# PE_CAM_EZ_Bridge.net
KiCad netlist of a schematic drawn in Altium Designer
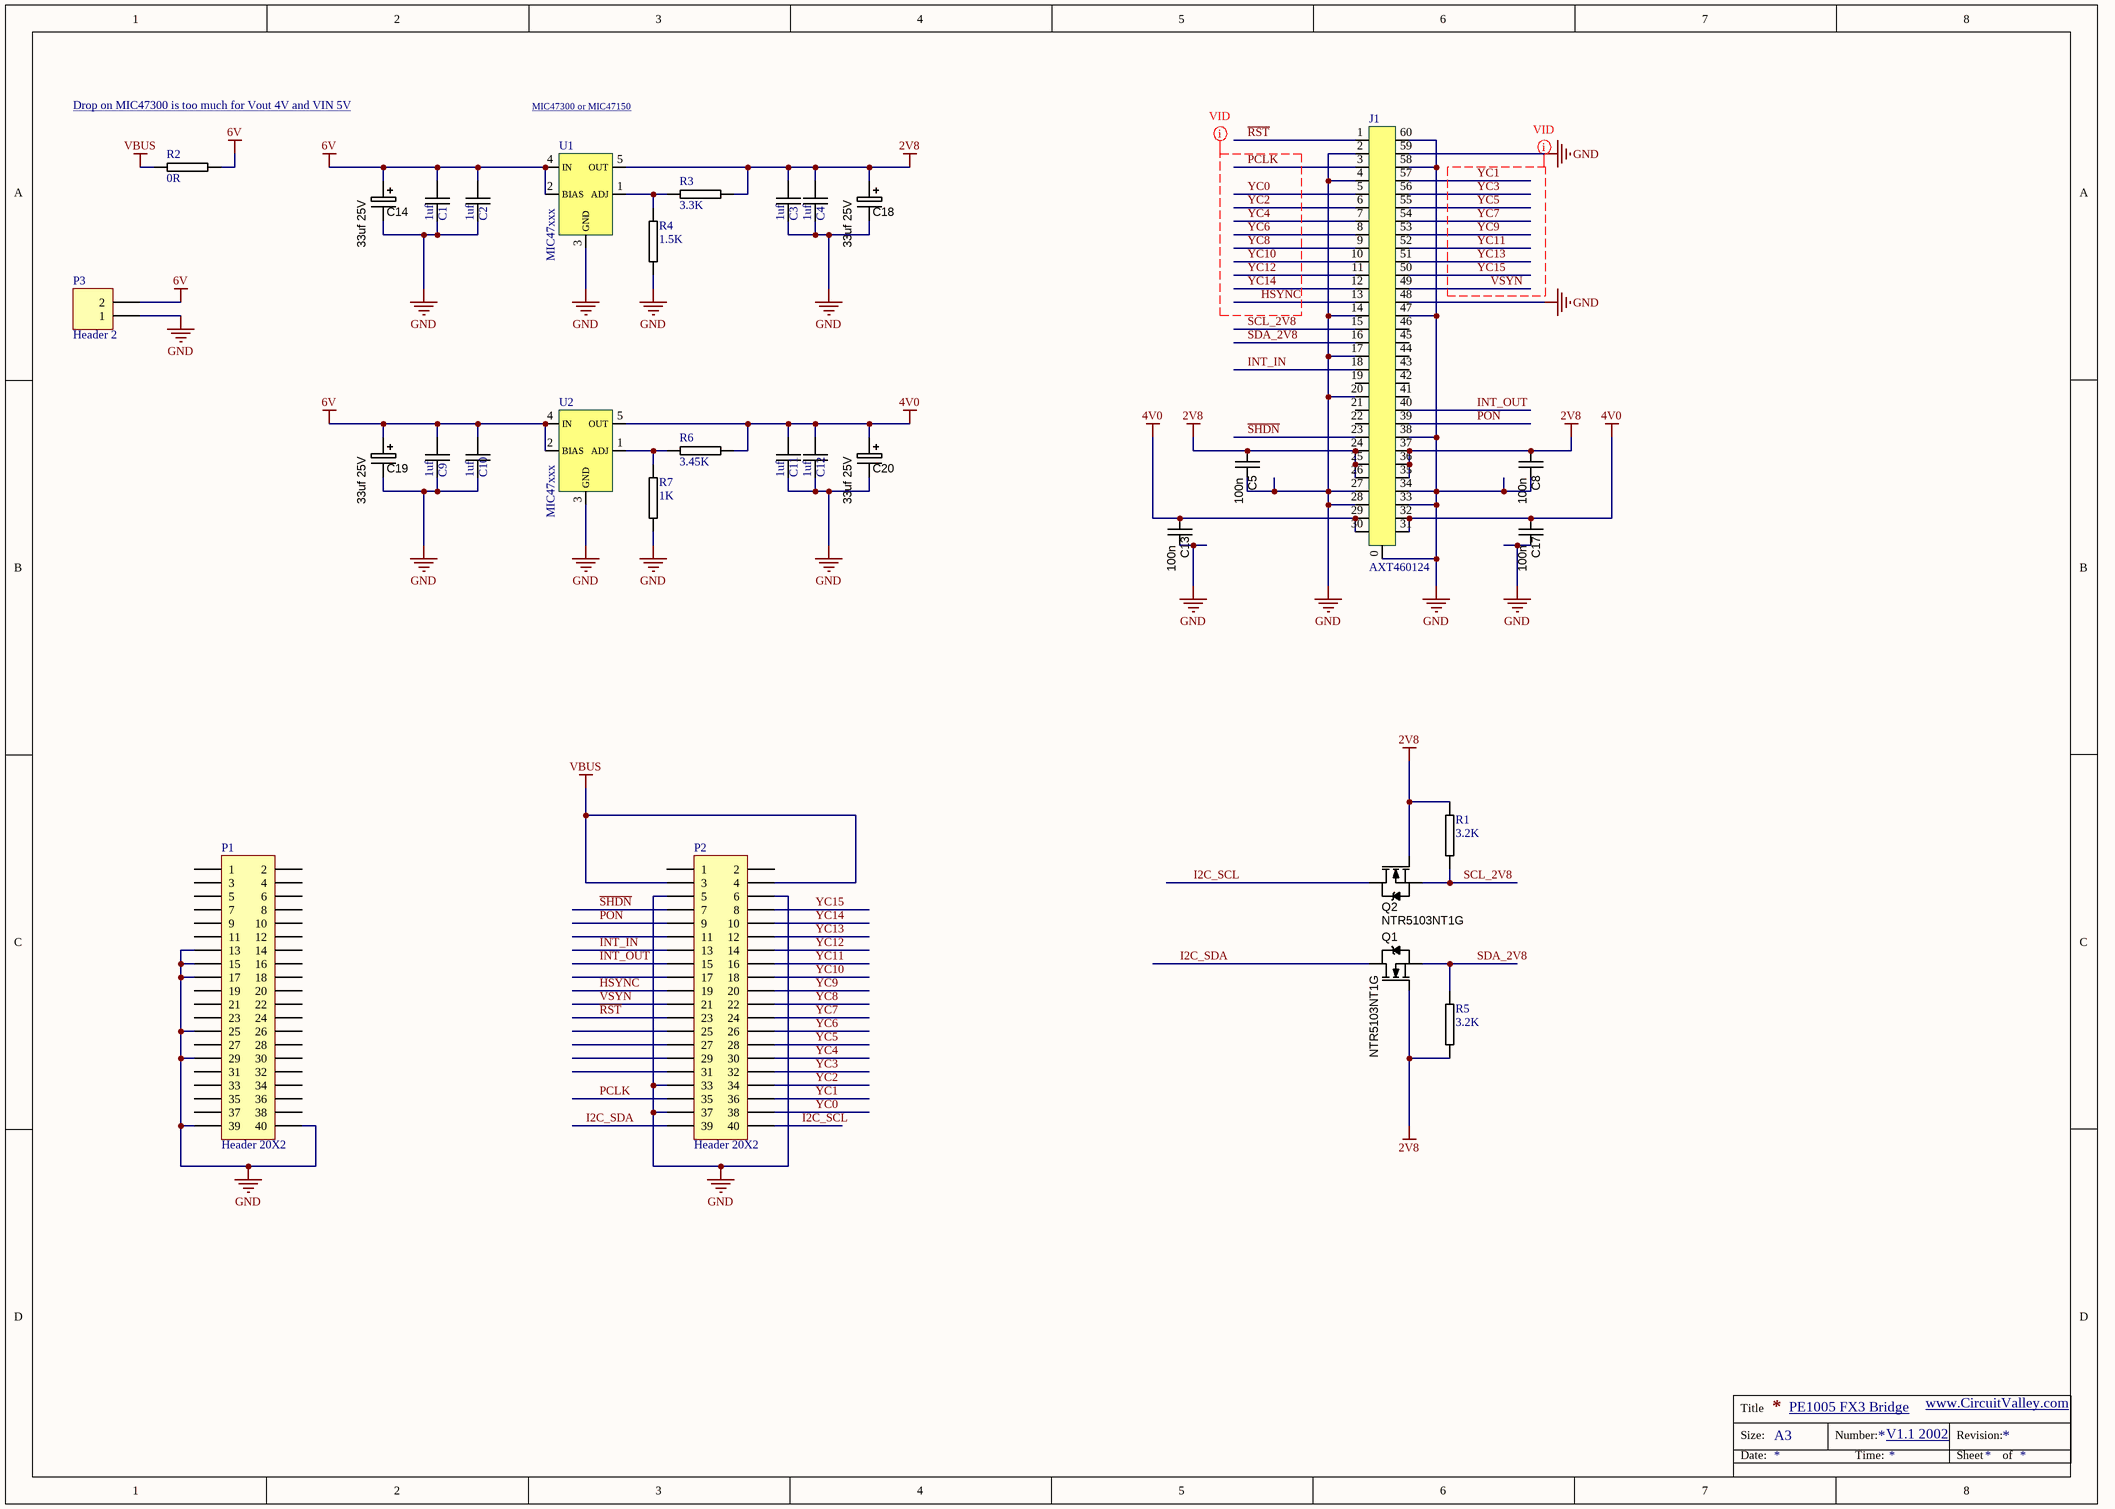
[diagram p0: PE_CAM_EZ_Bridge.SchDoc]

(export (version "E")
  (design (tool "Eeschema 10.0.6"))
  (components
    (comp (ref "C1")
      (value "1uf")
      (footprint "0805C-TBD")
      (description "CAPACITOR 0805 CERAMIC VALUE TO BE DETERMINED")
      (libsource (lib "Generic") (part "0805C-TBD"))
    )
    (comp (ref "C2")
      (value "1uf")
      (footprint "0805C-TBD")
      (description "CAPACITOR 0805 CERAMIC VALUE TO BE DETERMINED")
      (libsource (lib "Generic") (part "0805C-TBD"))
    )
    (comp (ref "C3")
      (value "1uf")
      (footprint "0805C-TBD")
      (description "CAPACITOR 0805 CERAMIC VALUE TO BE DETERMINED")
      (libsource (lib "Generic") (part "0805C-TBD"))
    )
    (comp (ref "C4")
      (value "1uf")
      (footprint "0805C-TBD")
      (description "CAPACITOR 0805 CERAMIC VALUE TO BE DETERMINED")
      (libsource (lib "Generic") (part "0805C-TBD"))
    )
    (comp (ref "C5")
      (value "100n")
      (footprint "CAPC1608N")
      (description "Capacitor SMD Cer 10pF 5% 50V NP0 0603")
      (fields (field (name "TOLERANCE") "±5%") (field (name "PART") "C0603X104K5RAC"))
      (libsource (lib "PBL - Capacitors") (part "CAPC_10p_0603_NP0_1%_50V"))
    )
    (comp (ref "C8")
      (value "100n")
      (footprint "CAPC1608N")
      (description "Capacitor SMD Cer 10pF 5% 50V NP0 0603")
      (fields (field (name "TOLERANCE") "±5%") (field (name "PART") "C0603X104K5RAC"))
      (libsource (lib "PBL - Capacitors") (part "CAPC_10p_0603_NP0_1%_50V"))
    )
    (comp (ref "C9")
      (value "1uf")
      (footprint "0805C-TBD")
      (description "CAPACITOR 0805 CERAMIC VALUE TO BE DETERMINED")
      (libsource (lib "Generic") (part "0805C-TBD"))
    )
    (comp (ref "C10")
      (value "1uf")
      (footprint "0805C-TBD")
      (description "CAPACITOR 0805 CERAMIC VALUE TO BE DETERMINED")
      (libsource (lib "Generic") (part "0805C-TBD"))
    )
    (comp (ref "C11")
      (value "1uf")
      (footprint "0805C-TBD")
      (description "CAPACITOR 0805 CERAMIC VALUE TO BE DETERMINED")
      (libsource (lib "Generic") (part "0805C-TBD"))
    )
    (comp (ref "C12")
      (value "1uf")
      (footprint "0805C-TBD")
      (description "CAPACITOR 0805 CERAMIC VALUE TO BE DETERMINED")
      (libsource (lib "Generic") (part "0805C-TBD"))
    )
    (comp (ref "C13")
      (value "100n")
      (footprint "CAPC1608N")
      (description "Capacitor SMD Cer 10pF 5% 50V NP0 0603")
      (fields (field (name "TOLERANCE") "±5%") (field (name "PART") "C0603X104K5RAC"))
      (libsource (lib "PBL - Capacitors") (part "CAPC_10p_0603_NP0_1%_50V"))
    )
    (comp (ref "C14")
      (value "33uf 25V")
      (footprint "CAPMP7343X310N")
      (description "Capacitor SMD Tant 330uF 20% 6V3 2917")
      (fields
        (field (name "TOLERANCE") "±20%")
        (field (name "MANUFACTURER PART NUMBER") "T520D337M006ATE015")
      )
      (libsource (lib "PBL - Capacitors") (part "CAPT_330u_2917_6V3"))
    )
    (comp (ref "C17")
      (value "100n")
      (footprint "CAPC1608N")
      (description "Capacitor SMD Cer 10pF 5% 50V NP0 0603")
      (fields (field (name "TOLERANCE") "±5%") (field (name "PART") "C0603X104K5RAC"))
      (libsource (lib "PBL - Capacitors") (part "CAPC_10p_0603_NP0_1%_50V"))
    )
    (comp (ref "C18")
      (value "33uf 25V")
      (footprint "CAPMP7343X310N")
      (description "Capacitor SMD Tant 330uF 20% 6V3 2917")
      (fields
        (field (name "TOLERANCE") "±20%")
        (field (name "MANUFACTURER PART NUMBER") "T520D337M006ATE015")
      )
      (libsource (lib "PBL - Capacitors") (part "CAPT_330u_2917_6V3"))
    )
    (comp (ref "C19")
      (value "33uf 25V")
      (footprint "CAPMP7343X310N")
      (description "Capacitor SMD Tant 330uF 20% 6V3 2917")
      (fields
        (field (name "TOLERANCE") "±20%")
        (field (name "MANUFACTURER PART NUMBER") "T520D337M006ATE015")
      )
      (libsource (lib "PBL - Capacitors") (part "CAPT_330u_2917_6V3"))
    )
    (comp (ref "C20")
      (value "33uf 25V")
      (footprint "CAPMP7343X310N")
      (description "Capacitor SMD Tant 330uF 20% 6V3 2917")
      (fields
        (field (name "TOLERANCE") "±20%")
        (field (name "MANUFACTURER PART NUMBER") "T520D337M006ATE015")
      )
      (libsource (lib "PBL - Capacitors") (part "CAPT_330u_2917_6V3"))
    )
    (comp (ref "J1")
      (value "AXT460124")
      (footprint "AXT460124")
      (libsource (lib "cvlib") (part "Connector 60 Pin"))
    )
    (comp (ref "P1")
      (value "Header 20X2")
      (footprint "HDR2X20")
      (description "Header, 20-Pin, Dual row")
      (fields (field (name "PUBLISHER") "Altium Limited"))
      (libsource (lib "Miscellaneous Connectors") (part "Header 20X2"))
    )
    (comp (ref "P2")
      (value "Header 20X2")
      (footprint "HDR2X20")
      (description "Header, 20-Pin, Dual row")
      (fields (field (name "PUBLISHER") "Altium Limited"))
      (libsource (lib "Miscellaneous Connectors") (part "Header 20X2"))
    )
    (comp (ref "P3")
      (value "Header 2")
      (footprint "HDR1X2")
      (description "Header, 2-Pin")
      (fields (field (name "PUBLISHER") "Altium Limited"))
      (libsource (lib "Miscellaneous Connectors") (part "Header 2"))
    )
    (comp (ref "Q1")
      (value "NTR5103NT1G")
      (footprint "SOT23-3")
      (description "MOSFET SMD N-CH 100V 170mA SOT23-3")
      (libsource (lib "PBL - Transistors") (part "MOSFET_BSS123"))
    )
    (comp (ref "Q2")
      (value "NTR5103NT1G")
      (footprint "SOT23-3")
      (description "MOSFET SMD N-CH 100V 170mA SOT23-3")
      (libsource (lib "PBL - Transistors") (part "MOSFET_BSS123"))
    )
    (comp (ref "R1")
      (value "3.2K")
      (footprint "0805R-5K6")
      (description "RESISTOR 0805 1/4 WATT THIN FILM")
      (fields (field (name "PART") "RC0805FR-075K6L"))
      (libsource (lib "Generic") (part "0805R-5K6"))
    )
    (comp (ref "R2")
      (value "0R")
      (footprint "0805R-5K6")
      (description "RESISTOR 0805 1/4 WATT THIN FILM")
      (fields (field (name "PART") "RC0805FR-075K6L"))
      (libsource (lib "Generic") (part "0805R-5K6"))
    )
    (comp (ref "R3")
      (value "3.3K")
      (footprint "0805R-5K6")
      (description "RESISTOR 0805 1/4 WATT THIN FILM")
      (fields (field (name "PART") "RC0805FR-075K6L"))
      (libsource (lib "Generic") (part "0805R-5K6"))
    )
    (comp (ref "R4")
      (value "1.5K")
      (footprint "0805R-5K6")
      (description "RESISTOR 0805 1/4 WATT THIN FILM")
      (fields (field (name "PART") "RC0805FR-075K6L"))
      (libsource (lib "Generic") (part "0805R-5K6"))
    )
    (comp (ref "R5")
      (value "3.2K")
      (footprint "0805R-5K6")
      (description "RESISTOR 0805 1/4 WATT THIN FILM")
      (fields (field (name "PART") "RC0805FR-075K6L"))
      (libsource (lib "Generic") (part "0805R-5K6"))
    )
    (comp (ref "R6")
      (value "3.45K")
      (footprint "0805R-5K6")
      (description "RESISTOR 0805 1/4 WATT THIN FILM")
      (fields (field (name "PART") "RC0805FR-075K6L"))
      (libsource (lib "Generic") (part "0805R-5K6"))
    )
    (comp (ref "R7")
      (value "1K")
      (footprint "0805R-5K6")
      (description "RESISTOR 0805 1/4 WATT THIN FILM")
      (fields (field (name "PART") "RC0805FR-075K6L"))
      (libsource (lib "Generic") (part "0805R-5K6"))
    )
    (comp (ref "U1")
      (value "MIC47xxx")
      (footprint "TO-252-5 DPAK 5")
      (description "MIC47xxx Regulator")
      (libsource (lib "cvlib") (part "MIC47xxx"))
    )
    (comp (ref "U2")
      (value "MIC47xxx")
      (footprint "TO-252-5 DPAK 5")
      (description "MIC47xxx Regulator")
      (libsource (lib "cvlib") (part "MIC47xxx"))
    )
  )
  (nets
    (net (code "1") (name "/HSYNC") (class "Default")
      (node (ref "J1") (pin "13") (pinfunction "74_13") (pintype "passive"))
      (node (ref "P2") (pin "19") (pinfunction "19_19") (pintype "passive"))
    )
    (net (code "2") (name "/I2C_SCL") (class "Default")
      (node (ref "P2") (pin "40") (pinfunction "40_40") (pintype "passive"))
      (node (ref "Q2") (pin "3") (pinfunction "D_3") (pintype "passive"))
    )
    (net (code "3") (name "/I2C_SDA") (class "Default")
      (node (ref "P2") (pin "39") (pinfunction "39_39") (pintype "passive"))
      (node (ref "Q1") (pin "3") (pinfunction "D_3") (pintype "passive"))
    )
    (net (code "4") (name "/INT_IN") (class "Default")
      (node (ref "J1") (pin "18") (pinfunction "79_18") (pintype "passive"))
      (node (ref "P2") (pin "13") (pinfunction "13_13") (pintype "passive"))
    )
    (net (code "5") (name "/INT_OUT") (class "Default")
      (node (ref "J1") (pin "40") (pinfunction "101_40") (pintype "passive"))
      (node (ref "P2") (pin "15") (pinfunction "15_15") (pintype "passive"))
    )
    (net (code "6") (name "/PCLK") (class "Default")
      (node (ref "J1") (pin "3") (pinfunction "64_3") (pintype "passive"))
      (node (ref "P2") (pin "35") (pinfunction "35_35") (pintype "passive"))
    )
    (net (code "7") (name "/PON") (class "Default")
      (node (ref "J1") (pin "39") (pinfunction "100_39") (pintype "passive"))
      (node (ref "P2") (pin "9") (pinfunction "9_9") (pintype "passive"))
    )
    (net (code "8") (name "/SCL_2V8") (class "Default")
      (node (ref "J1") (pin "15") (pinfunction "76_15") (pintype "passive"))
      (node (ref "Q2") (pin "2") (pinfunction "S_2") (pintype "passive"))
      (node (ref "R1") (pin "2") (pintype "passive"))
    )
    (net (code "9") (name "/SDA_2V8") (class "Default")
      (node (ref "J1") (pin "16") (pinfunction "77_16") (pintype "passive"))
      (node (ref "Q1") (pin "2") (pinfunction "S_2") (pintype "passive"))
      (node (ref "R5") (pin "1") (pintype "passive"))
    )
    (net (code "10") (name "/VSYN") (class "Default")
      (node (ref "J1") (pin "49") (pinfunction "110_49") (pintype "passive"))
      (node (ref "P2") (pin "21") (pinfunction "21_21") (pintype "passive"))
    )
    (net (code "11") (name "/YC0") (class "Default")
      (node (ref "J1") (pin "5") (pinfunction "66_5") (pintype "passive"))
      (node (ref "P2") (pin "38") (pinfunction "38_38") (pintype "passive"))
    )
    (net (code "12") (name "/YC1") (class "Default")
      (node (ref "J1") (pin "57") (pinfunction "118_57") (pintype "passive"))
      (node (ref "P2") (pin "36") (pinfunction "36_36") (pintype "passive"))
    )
    (net (code "13") (name "/YC2") (class "Default")
      (node (ref "J1") (pin "6") (pinfunction "67_6") (pintype "passive"))
      (node (ref "P2") (pin "34") (pinfunction "34_34") (pintype "passive"))
    )
    (net (code "14") (name "/YC3") (class "Default")
      (node (ref "J1") (pin "56") (pinfunction "117_56") (pintype "passive"))
      (node (ref "P2") (pin "32") (pinfunction "32_32") (pintype "passive"))
    )
    (net (code "15") (name "/YC4") (class "Default")
      (node (ref "J1") (pin "7") (pinfunction "68_7") (pintype "passive"))
      (node (ref "P2") (pin "30") (pinfunction "30_30") (pintype "passive"))
    )
    (net (code "16") (name "/YC5") (class "Default")
      (node (ref "J1") (pin "55") (pinfunction "116_55") (pintype "passive"))
      (node (ref "P2") (pin "28") (pinfunction "28_28") (pintype "passive"))
    )
    (net (code "17") (name "/YC6") (class "Default")
      (node (ref "J1") (pin "8") (pinfunction "69_8") (pintype "passive"))
      (node (ref "P2") (pin "26") (pinfunction "26_26") (pintype "passive"))
    )
    (net (code "18") (name "/YC7") (class "Default")
      (node (ref "J1") (pin "54") (pinfunction "115_54") (pintype "passive"))
      (node (ref "P2") (pin "24") (pinfunction "24_24") (pintype "passive"))
    )
    (net (code "19") (name "/YC8") (class "Default")
      (node (ref "J1") (pin "9") (pinfunction "70_9") (pintype "passive"))
      (node (ref "P2") (pin "22") (pinfunction "22_22") (pintype "passive"))
    )
    (net (code "20") (name "/YC9") (class "Default")
      (node (ref "J1") (pin "53") (pinfunction "114_53") (pintype "passive"))
      (node (ref "P2") (pin "20") (pinfunction "20_20") (pintype "passive"))
    )
    (net (code "21") (name "/YC10") (class "Default")
      (node (ref "J1") (pin "10") (pinfunction "71_10") (pintype "passive"))
      (node (ref "P2") (pin "18") (pinfunction "18_18") (pintype "passive"))
    )
    (net (code "22") (name "/YC11") (class "Default")
      (node (ref "J1") (pin "52") (pinfunction "113_52") (pintype "passive"))
      (node (ref "P2") (pin "16") (pinfunction "16_16") (pintype "passive"))
    )
    (net (code "23") (name "/YC12") (class "Default")
      (node (ref "J1") (pin "11") (pinfunction "72_11") (pintype "passive"))
      (node (ref "P2") (pin "14") (pinfunction "14_14") (pintype "passive"))
    )
    (net (code "24") (name "/YC13") (class "Default")
      (node (ref "J1") (pin "51") (pinfunction "112_51") (pintype "passive"))
      (node (ref "P2") (pin "12") (pinfunction "12_12") (pintype "passive"))
    )
    (net (code "25") (name "/YC14") (class "Default")
      (node (ref "J1") (pin "12") (pinfunction "73_12") (pintype "passive"))
      (node (ref "P2") (pin "10") (pinfunction "10_10") (pintype "passive"))
    )
    (net (code "26") (name "/YC15") (class "Default")
      (node (ref "J1") (pin "50") (pinfunction "111_50") (pintype "passive"))
      (node (ref "P2") (pin "8") (pinfunction "8_8") (pintype "passive"))
    )
    (net (code "27") (name "/~{RST}") (class "Default")
      (node (ref "J1") (pin "1") (pinfunction "62_1") (pintype "passive"))
      (node (ref "P2") (pin "23") (pinfunction "23_23") (pintype "passive"))
    )
    (net (code "28") (name "/~{SHDN}") (class "Default")
      (node (ref "J1") (pin "23") (pinfunction "84_23") (pintype "passive"))
      (node (ref "P2") (pin "7") (pinfunction "7_7") (pintype "passive"))
    )
    (net (code "29") (name "2V8") (class "Default")
      (node (ref "C18") (pin "1") (pintype "passive"))
      (node (ref "C3") (pin "1") (pintype "passive"))
      (node (ref "C4") (pin "1") (pintype "passive"))
      (node (ref "C5") (pin "1") (pintype "passive"))
      (node (ref "C8") (pin "1") (pintype "passive"))
      (node (ref "J1") (pin "24") (pinfunction "85_24") (pintype "passive"))
      (node (ref "J1") (pin "25") (pinfunction "86_25") (pintype "passive"))
      (node (ref "J1") (pin "26") (pinfunction "87_26") (pintype "passive"))
      (node (ref "J1") (pin "35") (pinfunction "96_35") (pintype "passive"))
      (node (ref "J1") (pin "36") (pinfunction "97_36") (pintype "passive"))
      (node (ref "J1") (pin "37") (pinfunction "98_37") (pintype "passive"))
      (node (ref "Q1") (pin "1") (pinfunction "G_1") (pintype "passive"))
      (node (ref "Q2") (pin "1") (pinfunction "G_1") (pintype "passive"))
      (node (ref "R1") (pin "1") (pintype "passive"))
      (node (ref "R3") (pin "2") (pintype "passive"))
      (node (ref "R5") (pin "2") (pintype "passive"))
      (node (ref "U1") (pin "5") (pinfunction "OUT_5") (pintype "passive"))
    )
    (net (code "30") (name "4V0") (class "Default")
      (node (ref "C11") (pin "1") (pintype "passive"))
      (node (ref "C12") (pin "1") (pintype "passive"))
      (node (ref "C13") (pin "1") (pintype "passive"))
      (node (ref "C17") (pin "1") (pintype "passive"))
      (node (ref "C20") (pin "1") (pintype "passive"))
      (node (ref "J1") (pin "29") (pinfunction "90_29") (pintype "passive"))
      (node (ref "J1") (pin "30") (pinfunction "91_30") (pintype "passive"))
      (node (ref "J1") (pin "31") (pinfunction "92_31") (pintype "passive"))
      (node (ref "J1") (pin "32") (pinfunction "93_32") (pintype "passive"))
      (node (ref "R6") (pin "2") (pintype "passive"))
      (node (ref "U2") (pin "5") (pinfunction "OUT_5") (pintype "passive"))
    )
    (net (code "31") (name "6V") (class "Default")
      (node (ref "C1") (pin "1") (pintype "passive"))
      (node (ref "C10") (pin "1") (pintype "passive"))
      (node (ref "C14") (pin "1") (pintype "passive"))
      (node (ref "C19") (pin "1") (pintype "passive"))
      (node (ref "C2") (pin "1") (pintype "passive"))
      (node (ref "C9") (pin "1") (pintype "passive"))
      (node (ref "P3") (pin "2") (pinfunction "2_2") (pintype "passive"))
      (node (ref "R2") (pin "2") (pintype "passive"))
      (node (ref "U1") (pin "2") (pinfunction "BIAS_2") (pintype "passive"))
      (node (ref "U1") (pin "4") (pinfunction "IN_4") (pintype "passive"))
      (node (ref "U2") (pin "2") (pinfunction "BIAS_2") (pintype "passive"))
      (node (ref "U2") (pin "4") (pinfunction "IN_4") (pintype "passive"))
    )
    (net (code "32") (name "GND") (class "Default")
      (node (ref "C1") (pin "2") (pintype "passive"))
      (node (ref "C10") (pin "2") (pintype "passive"))
      (node (ref "C11") (pin "2") (pintype "passive"))
      (node (ref "C12") (pin "2") (pintype "passive"))
      (node (ref "C13") (pin "2") (pintype "passive"))
      (node (ref "C14") (pin "2") (pintype "passive"))
      (node (ref "C17") (pin "2") (pintype "passive"))
      (node (ref "C18") (pin "2") (pintype "passive"))
      (node (ref "C19") (pin "2") (pintype "passive"))
      (node (ref "C2") (pin "2") (pintype "passive"))
      (node (ref "C20") (pin "2") (pintype "passive"))
      (node (ref "C3") (pin "2") (pintype "passive"))
      (node (ref "C4") (pin "2") (pintype "passive"))
      (node (ref "C5") (pin "2") (pintype "passive"))
      (node (ref "C8") (pin "2") (pintype "passive"))
      (node (ref "C9") (pin "2") (pintype "passive"))
      (node (ref "J1") (pin "0") (pinfunction "61_0") (pintype "passive"))
      (node (ref "J1") (pin "14") (pinfunction "75_14") (pintype "passive"))
      (node (ref "J1") (pin "17") (pinfunction "78_17") (pintype "passive"))
      (node (ref "J1") (pin "2") (pinfunction "63_2") (pintype "passive"))
      (node (ref "J1") (pin "20") (pinfunction "81_20") (pintype "passive"))
      (node (ref "J1") (pin "27") (pinfunction "88_27") (pintype "passive"))
      (node (ref "J1") (pin "28") (pinfunction "89_28") (pintype "passive"))
      (node (ref "J1") (pin "33") (pinfunction "94_33") (pintype "passive"))
      (node (ref "J1") (pin "34") (pinfunction "95_34") (pintype "passive"))
      (node (ref "J1") (pin "38") (pinfunction "99_38") (pintype "passive"))
      (node (ref "J1") (pin "4") (pinfunction "65_4") (pintype "passive"))
      (node (ref "J1") (pin "47") (pinfunction "108_47") (pintype "passive"))
      (node (ref "J1") (pin "48") (pinfunction "109_48") (pintype "passive"))
      (node (ref "J1") (pin "58") (pinfunction "119_58") (pintype "passive"))
      (node (ref "J1") (pin "59") (pinfunction "120_59") (pintype "passive"))
      (node (ref "J1") (pin "60") (pinfunction "121_60") (pintype "passive"))
      (node (ref "P1") (pin "13") (pinfunction "13_13") (pintype "passive"))
      (node (ref "P1") (pin "15") (pinfunction "15_15") (pintype "passive"))
      (node (ref "P1") (pin "17") (pinfunction "17_17") (pintype "passive"))
      (node (ref "P1") (pin "25") (pinfunction "25_25") (pintype "passive"))
      (node (ref "P1") (pin "29") (pinfunction "29_29") (pintype "passive"))
      (node (ref "P1") (pin "39") (pinfunction "39_39") (pintype "passive"))
      (node (ref "P1") (pin "40") (pinfunction "40_40") (pintype "passive"))
      (node (ref "P2") (pin "33") (pinfunction "33_33") (pintype "passive"))
      (node (ref "P2") (pin "37") (pinfunction "37_37") (pintype "passive"))
      (node (ref "P2") (pin "5") (pinfunction "5_5") (pintype "passive"))
      (node (ref "P2") (pin "6") (pinfunction "6_6") (pintype "passive"))
      (node (ref "P3") (pin "1") (pinfunction "1_1") (pintype "passive"))
      (node (ref "R4") (pin "2") (pintype "passive"))
      (node (ref "R7") (pin "2") (pintype "passive"))
      (node (ref "U1") (pin "3") (pinfunction "GND_3") (pintype "passive"))
      (node (ref "U2") (pin "3") (pinfunction "GND_3") (pintype "passive"))
    )
    (net (code "33") (name "Net-(U1-ADJ)") (class "Default")
      (node (ref "R3") (pin "1") (pintype "passive"))
      (node (ref "R4") (pin "1") (pintype "passive"))
      (node (ref "U1") (pin "1") (pinfunction "ADJ_1") (pintype "passive"))
    )
    (net (code "34") (name "Net-(U2-ADJ)") (class "Default")
      (node (ref "R6") (pin "1") (pintype "passive"))
      (node (ref "R7") (pin "1") (pintype "passive"))
      (node (ref "U2") (pin "1") (pinfunction "ADJ_1") (pintype "passive"))
    )
    (net (code "35") (name "VBUS") (class "Default")
      (node (ref "P2") (pin "3") (pinfunction "3_3") (pintype "passive"))
      (node (ref "P2") (pin "4") (pinfunction "4_4") (pintype "passive"))
      (node (ref "R2") (pin "1") (pintype "passive"))
    )
    (net (code "36") (name "unconnected-(J1-80-Pad19)") (class "Default")
      (node (ref "J1") (pin "19") (pinfunction "80_19") (pintype "passive"))
    )
    (net (code "37") (name "unconnected-(J1-82-Pad21)") (class "Default")
      (node (ref "J1") (pin "21") (pinfunction "82_21") (pintype "passive"))
    )
    (net (code "38") (name "unconnected-(J1-83-Pad22)") (class "Default")
      (node (ref "J1") (pin "22") (pinfunction "83_22") (pintype "passive"))
    )
    (net (code "39") (name "unconnected-(J1-102-Pad41)") (class "Default")
      (node (ref "J1") (pin "41") (pinfunction "102_41") (pintype "passive"))
    )
    (net (code "40") (name "unconnected-(J1-103-Pad42)") (class "Default")
      (node (ref "J1") (pin "42") (pinfunction "103_42") (pintype "passive"))
    )
    (net (code "41") (name "unconnected-(J1-104-Pad43)") (class "Default")
      (node (ref "J1") (pin "43") (pinfunction "104_43") (pintype "passive"))
    )
    (net (code "42") (name "unconnected-(J1-105-Pad44)") (class "Default")
      (node (ref "J1") (pin "44") (pinfunction "105_44") (pintype "passive"))
    )
    (net (code "43") (name "unconnected-(J1-106-Pad45)") (class "Default")
      (node (ref "J1") (pin "45") (pinfunction "106_45") (pintype "passive"))
    )
    (net (code "44") (name "unconnected-(J1-107-Pad46)") (class "Default")
      (node (ref "J1") (pin "46") (pinfunction "107_46") (pintype "passive"))
    )
    (net (code "45") (name "unconnected-(P1-Pad1)") (class "Default")
      (node (ref "P1") (pin "1") (pinfunction "1_1") (pintype "passive"))
    )
    (net (code "46") (name "unconnected-(P1-Pad2)") (class "Default")
      (node (ref "P1") (pin "2") (pinfunction "2_2") (pintype "passive"))
    )
    (net (code "47") (name "unconnected-(P1-Pad3)") (class "Default")
      (node (ref "P1") (pin "3") (pinfunction "3_3") (pintype "passive"))
    )
    (net (code "48") (name "unconnected-(P1-Pad4)") (class "Default")
      (node (ref "P1") (pin "4") (pinfunction "4_4") (pintype "passive"))
    )
    (net (code "49") (name "unconnected-(P1-Pad5)") (class "Default")
      (node (ref "P1") (pin "5") (pinfunction "5_5") (pintype "passive"))
    )
    (net (code "50") (name "unconnected-(P1-Pad6)") (class "Default")
      (node (ref "P1") (pin "6") (pinfunction "6_6") (pintype "passive"))
    )
    (net (code "51") (name "unconnected-(P1-Pad7)") (class "Default")
      (node (ref "P1") (pin "7") (pinfunction "7_7") (pintype "passive"))
    )
    (net (code "52") (name "unconnected-(P1-Pad8)") (class "Default")
      (node (ref "P1") (pin "8") (pinfunction "8_8") (pintype "passive"))
    )
    (net (code "53") (name "unconnected-(P1-Pad9)") (class "Default")
      (node (ref "P1") (pin "9") (pinfunction "9_9") (pintype "passive"))
    )
    (net (code "54") (name "unconnected-(P1-Pad10)") (class "Default")
      (node (ref "P1") (pin "10") (pinfunction "10_10") (pintype "passive"))
    )
    (net (code "55") (name "unconnected-(P1-Pad11)") (class "Default")
      (node (ref "P1") (pin "11") (pinfunction "11_11") (pintype "passive"))
    )
    (net (code "56") (name "unconnected-(P1-Pad12)") (class "Default")
      (node (ref "P1") (pin "12") (pinfunction "12_12") (pintype "passive"))
    )
    (net (code "57") (name "unconnected-(P1-Pad14)") (class "Default")
      (node (ref "P1") (pin "14") (pinfunction "14_14") (pintype "passive"))
    )
    (net (code "58") (name "unconnected-(P1-Pad16)") (class "Default")
      (node (ref "P1") (pin "16") (pinfunction "16_16") (pintype "passive"))
    )
    (net (code "59") (name "unconnected-(P1-Pad18)") (class "Default")
      (node (ref "P1") (pin "18") (pinfunction "18_18") (pintype "passive"))
    )
    (net (code "60") (name "unconnected-(P1-Pad19)") (class "Default")
      (node (ref "P1") (pin "19") (pinfunction "19_19") (pintype "passive"))
    )
    (net (code "61") (name "unconnected-(P1-Pad20)") (class "Default")
      (node (ref "P1") (pin "20") (pinfunction "20_20") (pintype "passive"))
    )
    (net (code "62") (name "unconnected-(P1-Pad21)") (class "Default")
      (node (ref "P1") (pin "21") (pinfunction "21_21") (pintype "passive"))
    )
    (net (code "63") (name "unconnected-(P1-Pad22)") (class "Default")
      (node (ref "P1") (pin "22") (pinfunction "22_22") (pintype "passive"))
    )
    (net (code "64") (name "unconnected-(P1-Pad23)") (class "Default")
      (node (ref "P1") (pin "23") (pinfunction "23_23") (pintype "passive"))
    )
    (net (code "65") (name "unconnected-(P1-Pad24)") (class "Default")
      (node (ref "P1") (pin "24") (pinfunction "24_24") (pintype "passive"))
    )
    (net (code "66") (name "unconnected-(P1-Pad26)") (class "Default")
      (node (ref "P1") (pin "26") (pinfunction "26_26") (pintype "passive"))
    )
    (net (code "67") (name "unconnected-(P1-Pad27)") (class "Default")
      (node (ref "P1") (pin "27") (pinfunction "27_27") (pintype "passive"))
    )
    (net (code "68") (name "unconnected-(P1-Pad28)") (class "Default")
      (node (ref "P1") (pin "28") (pinfunction "28_28") (pintype "passive"))
    )
    (net (code "69") (name "unconnected-(P1-Pad30)") (class "Default")
      (node (ref "P1") (pin "30") (pinfunction "30_30") (pintype "passive"))
    )
    (net (code "70") (name "unconnected-(P1-Pad31)") (class "Default")
      (node (ref "P1") (pin "31") (pinfunction "31_31") (pintype "passive"))
    )
    (net (code "71") (name "unconnected-(P1-Pad32)") (class "Default")
      (node (ref "P1") (pin "32") (pinfunction "32_32") (pintype "passive"))
    )
    (net (code "72") (name "unconnected-(P1-Pad33)") (class "Default")
      (node (ref "P1") (pin "33") (pinfunction "33_33") (pintype "passive"))
    )
    (net (code "73") (name "unconnected-(P1-Pad34)") (class "Default")
      (node (ref "P1") (pin "34") (pinfunction "34_34") (pintype "passive"))
    )
    (net (code "74") (name "unconnected-(P1-Pad35)") (class "Default")
      (node (ref "P1") (pin "35") (pinfunction "35_35") (pintype "passive"))
    )
    (net (code "75") (name "unconnected-(P1-Pad36)") (class "Default")
      (node (ref "P1") (pin "36") (pinfunction "36_36") (pintype "passive"))
    )
    (net (code "76") (name "unconnected-(P1-Pad37)") (class "Default")
      (node (ref "P1") (pin "37") (pinfunction "37_37") (pintype "passive"))
    )
    (net (code "77") (name "unconnected-(P1-Pad38)") (class "Default")
      (node (ref "P1") (pin "38") (pinfunction "38_38") (pintype "passive"))
    )
    (net (code "78") (name "unconnected-(P2-Pad1)") (class "Default")
      (node (ref "P2") (pin "1") (pinfunction "1_1") (pintype "passive"))
    )
    (net (code "79") (name "unconnected-(P2-Pad2)") (class "Default")
      (node (ref "P2") (pin "2") (pinfunction "2_2") (pintype "passive"))
    )
    (net (code "80") (name "unconnected-(P2-Pad11)") (class "Default")
      (node (ref "P2") (pin "11") (pinfunction "11_11") (pintype "passive"))
    )
    (net (code "81") (name "unconnected-(P2-Pad17)") (class "Default")
      (node (ref "P2") (pin "17") (pinfunction "17_17") (pintype "passive"))
    )
    (net (code "82") (name "unconnected-(P2-Pad25)") (class "Default")
      (node (ref "P2") (pin "25") (pinfunction "25_25") (pintype "passive"))
    )
    (net (code "83") (name "unconnected-(P2-Pad27)") (class "Default")
      (node (ref "P2") (pin "27") (pinfunction "27_27") (pintype "passive"))
    )
    (net (code "84") (name "unconnected-(P2-Pad29)") (class "Default")
      (node (ref "P2") (pin "29") (pinfunction "29_29") (pintype "passive"))
    )
    (net (code "85") (name "unconnected-(P2-Pad31)") (class "Default")
      (node (ref "P2") (pin "31") (pinfunction "31_31") (pintype "passive"))
    )
  )
)
